# 5Vto12V_Boost_Converter_Motors.net
KiCad netlist of a schematic drawn in Altium Designer
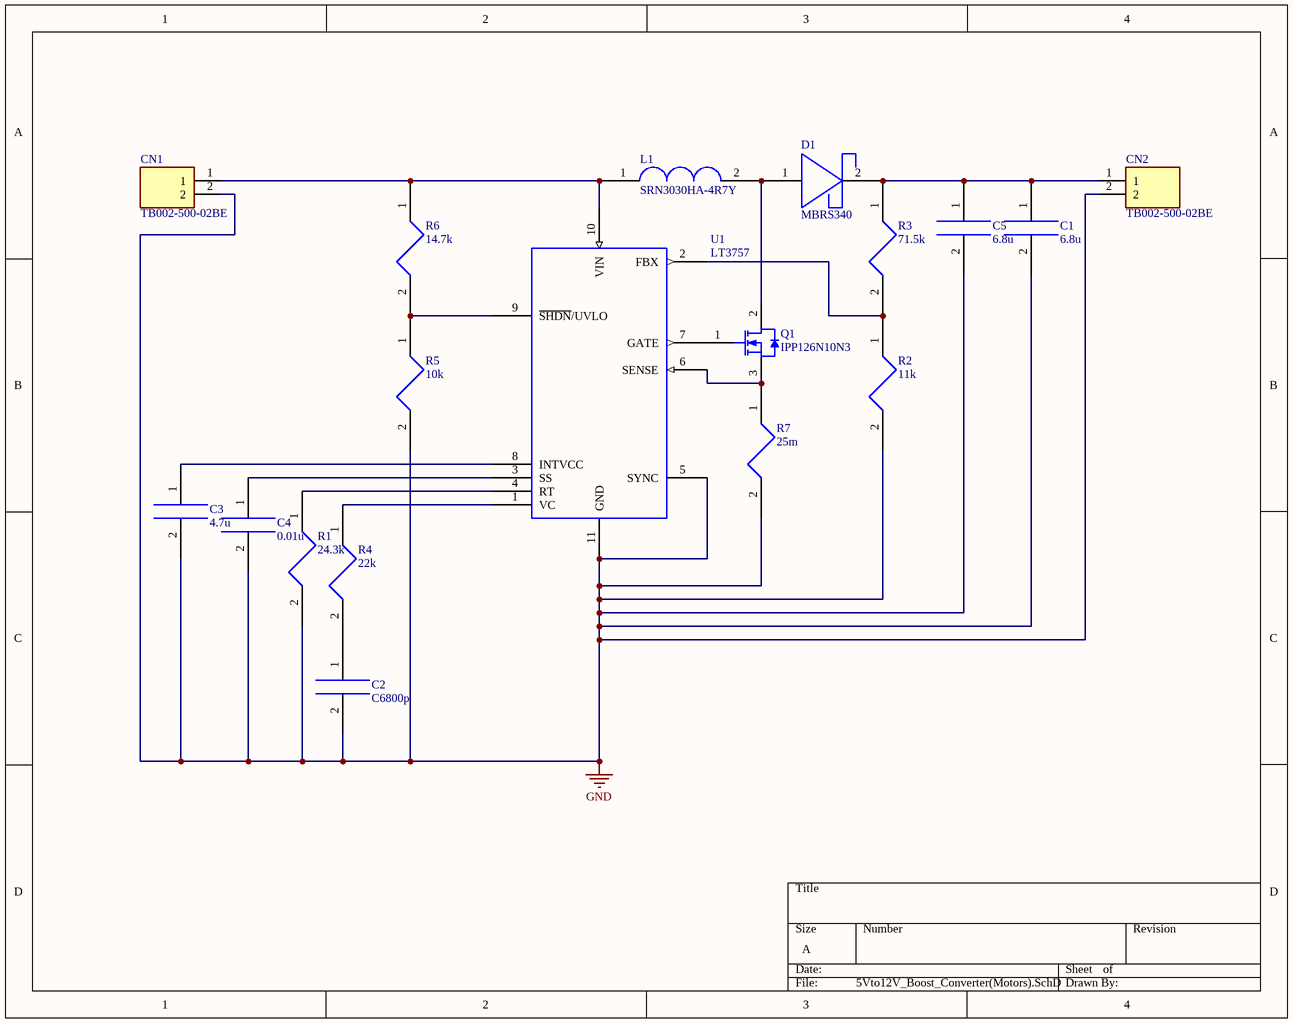
[diagram p0: 5Vto12V_Boost_Converter(Motors).SchDoc]

(export (version "E")
  (design (tool "Eeschema 10.0.6"))
  (components
    (comp (ref "C1") (value "6.8u") (footprint "C6.8u") (libsource (lib "Schlib1") (part "C6.8u")))
    (comp (ref "C2") (value "C6800p") (footprint "C6800p") (libsource (lib "Schlib1") (part "C6800p")))
    (comp (ref "C3") (value "4.7u") (footprint "C4.7u") (libsource (lib "Schlib1") (part "C4.7u")))
    (comp (ref "C4")
      (value "0.01u")
      (footprint "C0.01u")
      (description "SMD 0.01uF Capacitor")
      (libsource (lib "Schlib1") (part "C0.01u"))
    )
    (comp (ref "C5") (value "6.8u") (footprint "C6.8u") (libsource (lib "Schlib1") (part "C6.8u")))
    (comp (ref "CN1")
      (value "TB002-500-02BE")
      (footprint "TB002-500-02BE")
      (libsource (lib "") (part "TB002-500-02BE_1"))
    )
    (comp (ref "CN2")
      (value "TB002-500-02BE")
      (footprint "TB002-500-02BE")
      (libsource (lib "Schlib1") (part "TB002-500-02BE"))
    )
    (comp (ref "D1") (value "MBRS340") (footprint "MBRS340") (libsource (lib "Schlib1") (part "MBRS340")))
    (comp (ref "L1")
      (value "SRN3030HA-4R7Y")
      (footprint "SRN3030HA-4R7Y(Inductor-1)")
      (libsource (lib "Schlib1") (part "SRN3030HA-4R7Y(Inductor-1)"))
    )
    (comp (ref "Q1")
      (value "IPP126N10N3")
      (footprint "IPP126N10N3")
      (libsource (lib "Schlib1") (part "IPP126N10N3"))
    )
    (comp (ref "R1") (value "24.3k") (footprint "R24.3k") (libsource (lib "Schlib1") (part "R24.3k")))
    (comp (ref "R2") (value "11k") (footprint "R11k") (libsource (lib "Schlib1") (part "R11k")))
    (comp (ref "R3") (value "71.5k") (footprint "R71.5k") (libsource (lib "Schlib1") (part "R71.5k")))
    (comp (ref "R4") (value "22k") (footprint "R22k") (libsource (lib "Schlib1") (part "R22k")))
    (comp (ref "R5")
      (value "10k")
      (footprint "R10k")
      (description "SMD 10k Resistor")
      (libsource (lib "Schlib1") (part "R10k"))
    )
    (comp (ref "R6") (value "14.7k") (footprint "R14.7k") (libsource (lib "Schlib1") (part "R14.7k")))
    (comp (ref "R7") (value "25m") (footprint "R25m") (libsource (lib "Schlib1") (part "R25m")))
    (comp (ref "U1") (value "LT3757") (footprint "LT3757") (libsource (lib "Schlib1") (part "LT3757")))
  )
  (nets
    (net (code "1") (name "GND") (class "Default")
      (node (ref "C1") (pin "2") (pintype "passive"))
      (node (ref "C2") (pin "2") (pintype "passive"))
      (node (ref "C3") (pin "2") (pintype "passive"))
      (node (ref "C4") (pin "2") (pintype "passive"))
      (node (ref "C5") (pin "2") (pintype "passive"))
      (node (ref "CN1") (pin "2") (pinfunction "2_2") (pintype "passive"))
      (node (ref "CN2") (pin "2") (pinfunction "2_2") (pintype "passive"))
      (node (ref "R1") (pin "2") (pintype "passive"))
      (node (ref "R2") (pin "2") (pintype "passive"))
      (node (ref "R5") (pin "2") (pintype "passive"))
      (node (ref "R7") (pin "2") (pintype "passive"))
      (node (ref "U1") (pin "11") (pinfunction "GND_11") (pintype "passive"))
      (node (ref "U1") (pin "5") (pinfunction "SYNC_5") (pintype "passive"))
    )
    (net (code "2") (name "Net-(C1-Pad1)") (class "Default")
      (node (ref "C1") (pin "1") (pintype "passive"))
      (node (ref "C5") (pin "1") (pintype "passive"))
      (node (ref "CN2") (pin "1") (pinfunction "1_1") (pintype "passive"))
      (node (ref "D1") (pin "2") (pintype "passive"))
      (node (ref "R3") (pin "1") (pintype "passive"))
    )
    (net (code "3") (name "Net-(C2-Pad1)") (class "Default")
      (node (ref "C2") (pin "1") (pintype "passive"))
      (node (ref "R4") (pin "2") (pintype "passive"))
    )
    (net (code "4") (name "Net-(Q1-DRAIN)") (class "Default")
      (node (ref "D1") (pin "1") (pintype "passive"))
      (node (ref "L1") (pin "2") (pintype "passive"))
      (node (ref "Q1") (pin "2") (pinfunction "DRAIN_2") (pintype "passive"))
    )
    (net (code "5") (name "Net-(Q1-GATE)") (class "Default")
      (node (ref "Q1") (pin "1") (pinfunction "GATE_1") (pintype "passive"))
      (node (ref "U1") (pin "7") (pinfunction "GATE_7") (pintype "output"))
    )
    (net (code "6") (name "Net-(Q1-SOURCE)") (class "Default")
      (node (ref "Q1") (pin "3") (pinfunction "SOURCE_3") (pintype "passive"))
      (node (ref "R7") (pin "1") (pintype "passive"))
      (node (ref "U1") (pin "6") (pinfunction "SENSE_6") (pintype "input"))
    )
    (net (code "7") (name "Net-(U1-FBX)") (class "Default")
      (node (ref "R2") (pin "1") (pintype "passive"))
      (node (ref "R3") (pin "2") (pintype "passive"))
      (node (ref "U1") (pin "2") (pinfunction "FBX_2") (pintype "output"))
    )
    (net (code "8") (name "Net-(U1-INTVCC)") (class "Default")
      (node (ref "C3") (pin "1") (pintype "passive"))
      (node (ref "U1") (pin "8") (pinfunction "INTVCC_8") (pintype "passive"))
    )
    (net (code "9") (name "Net-(U1-RT)") (class "Default")
      (node (ref "R1") (pin "1") (pintype "passive"))
      (node (ref "U1") (pin "4") (pinfunction "RT_4") (pintype "passive"))
    )
    (net (code "10") (name "Net-(U1-SS)") (class "Default")
      (node (ref "C4") (pin "1") (pintype "passive"))
      (node (ref "U1") (pin "3") (pinfunction "SS_3") (pintype "passive"))
    )
    (net (code "11") (name "Net-(U1-VC)") (class "Default")
      (node (ref "R4") (pin "1") (pintype "passive"))
      (node (ref "U1") (pin "1") (pinfunction "VC_1") (pintype "passive"))
    )
    (net (code "12") (name "Net-(U1-VIN)") (class "Default")
      (node (ref "CN1") (pin "1") (pinfunction "1_1") (pintype "passive"))
      (node (ref "L1") (pin "1") (pintype "passive"))
      (node (ref "R6") (pin "1") (pintype "passive"))
      (node (ref "U1") (pin "10") (pinfunction "VIN_10") (pintype "input"))
    )
    (net (code "13") (name "Net-(U1-~{SHDN}{slash}UVLO)") (class "Default")
      (node (ref "R5") (pin "1") (pintype "passive"))
      (node (ref "R6") (pin "2") (pintype "passive"))
      (node (ref "U1") (pin "9") (pinfunction "~{SHDN}/UVLO_9") (pintype "passive"))
    )
  )
)
